# OErs_Drone.net
KiCad netlist of a schematic drawn in Altium Designer
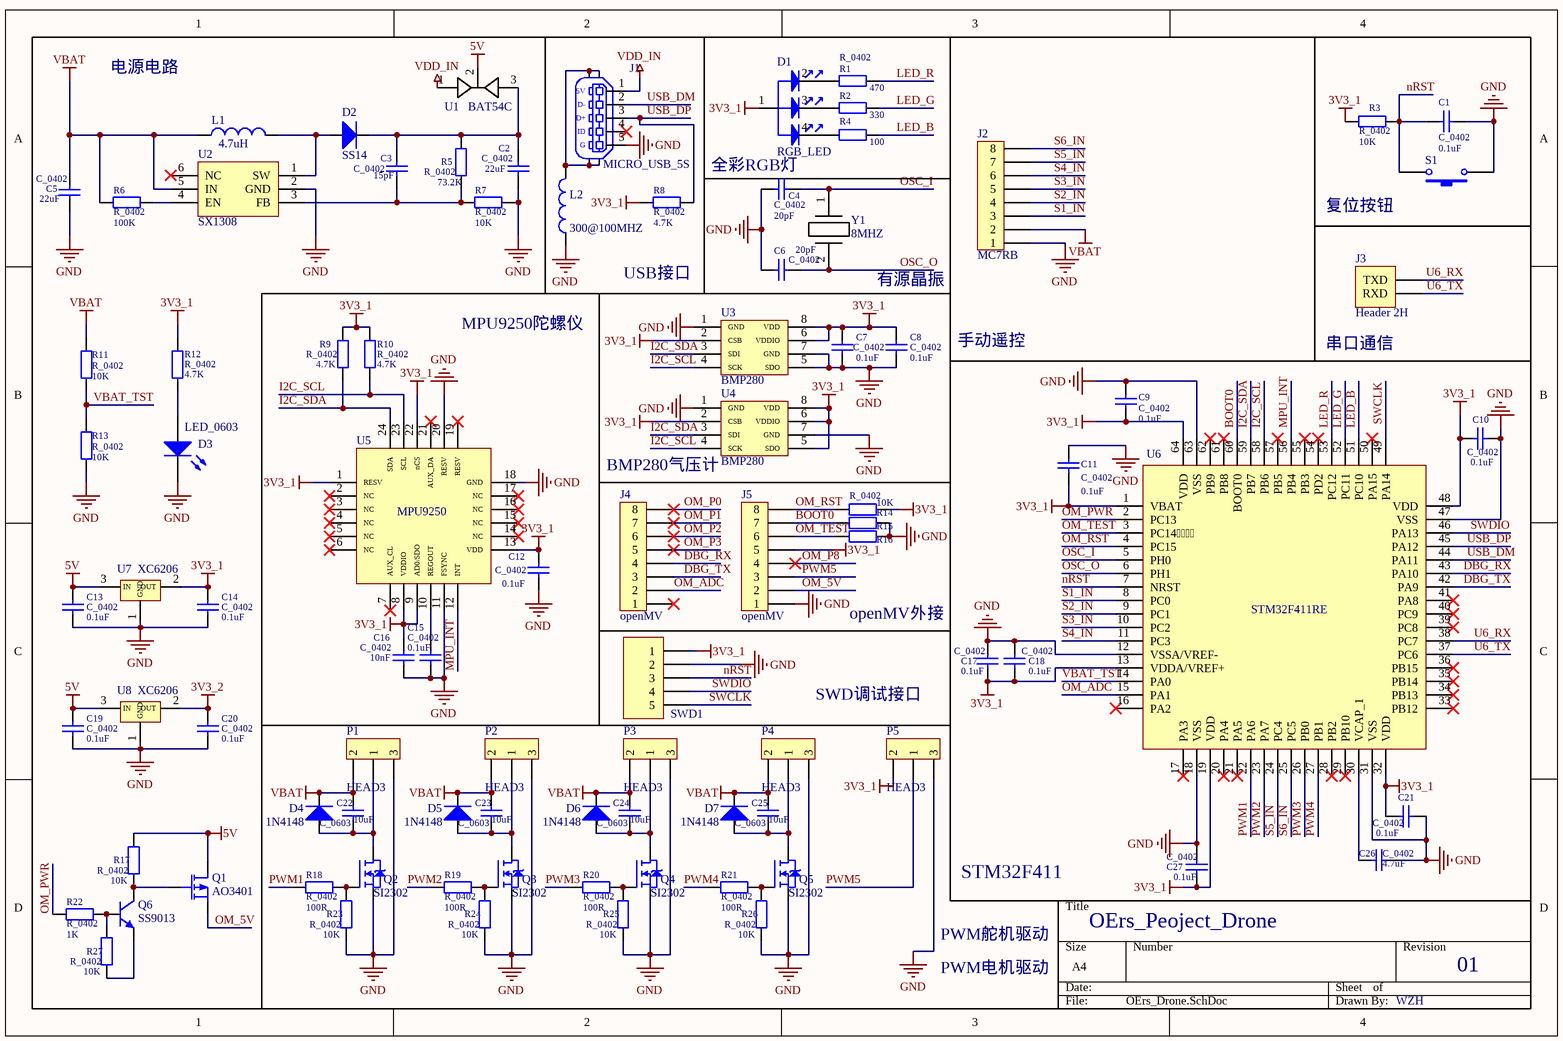
[diagram p0: OErs_Drone.SchDoc]

(export (version "E")
  (design (tool "Eeschema 10.0.6"))
  (components
    (comp (ref "C1")
      (value "C_0402")
      (footprint "C0402")
      (description "Capacitor")
      (fields (field (name "ALTIUM_VALUE") "0.1uF") (field (name "PUBLISHER") "Altium Limited"))
      (libsource (lib "Miscellaneous Devices") (part "Cap"))
    )
    (comp (ref "C2")
      (value "C_0402")
      (footprint "C0402")
      (description "Capacitor")
      (fields (field (name "ALTIUM_VALUE") "22uF") (field (name "PUBLISHER") "Altium Limited"))
      (libsource (lib "Miscellaneous Devices") (part "Cap"))
    )
    (comp (ref "C3")
      (value "C_0402")
      (footprint "C0402")
      (description "Capacitor")
      (fields (field (name "ALTIUM_VALUE") "15pF") (field (name "PUBLISHER") "Altium Limited"))
      (libsource (lib "Miscellaneous Devices") (part "Cap"))
    )
    (comp (ref "C4")
      (value "C_0402")
      (footprint "C0402")
      (description "Capacitor")
      (fields (field (name "ALTIUM_VALUE") "20pF") (field (name "PUBLISHER") "Altium Limited"))
      (libsource (lib "Miscellaneous Devices") (part "Cap"))
    )
    (comp (ref "C5")
      (value "C_0402")
      (footprint "C0402")
      (description "Capacitor")
      (fields (field (name "ALTIUM_VALUE") "22uF") (field (name "PUBLISHER") "Altium Limited"))
      (libsource (lib "Miscellaneous Devices") (part "Cap"))
    )
    (comp (ref "C6")
      (value "C_0402")
      (footprint "C0402")
      (description "Capacitor")
      (fields (field (name "ALTIUM_VALUE") "20pF") (field (name "PUBLISHER") "Altium Limited"))
      (libsource (lib "Miscellaneous Devices") (part "Cap"))
    )
    (comp (ref "C7")
      (value "C_0402")
      (footprint "C0402")
      (description "Capacitor")
      (fields (field (name "ALTIUM_VALUE") "0.1uF") (field (name "PUBLISHER") "Altium Limited"))
      (libsource (lib "Miscellaneous Devices") (part "Cap"))
    )
    (comp (ref "C8")
      (value "C_0402")
      (footprint "C0402")
      (description "Capacitor")
      (fields (field (name "ALTIUM_VALUE") "0.1uF") (field (name "PUBLISHER") "Altium Limited"))
      (libsource (lib "Miscellaneous Devices") (part "Cap"))
    )
    (comp (ref "C9")
      (value "C_0402")
      (footprint "C0402")
      (description "Capacitor")
      (fields (field (name "ALTIUM_VALUE") "0.1uF") (field (name "PUBLISHER") "Altium Limited"))
      (libsource (lib "Miscellaneous Devices") (part "Cap"))
    )
    (comp (ref "C10")
      (value "C_0402")
      (footprint "C0402")
      (description "Capacitor")
      (fields (field (name "ALTIUM_VALUE") "0.1uF") (field (name "PUBLISHER") "Altium Limited"))
      (libsource (lib "Miscellaneous Devices") (part "Cap"))
    )
    (comp (ref "C11")
      (value "C_0402")
      (footprint "C0402")
      (description "Capacitor")
      (fields (field (name "ALTIUM_VALUE") "0.1uF") (field (name "PUBLISHER") "Altium Limited"))
      (libsource (lib "Miscellaneous Devices") (part "Cap"))
    )
    (comp (ref "C12")
      (value "C_0402")
      (footprint "C0402")
      (description "Capacitor")
      (fields (field (name "ALTIUM_VALUE") "0.1uF") (field (name "PUBLISHER") "Altium Limited"))
      (libsource (lib "Miscellaneous Devices") (part "Cap"))
    )
    (comp (ref "C13")
      (value "C_0402")
      (footprint "C0402")
      (description "Capacitor")
      (fields (field (name "ALTIUM_VALUE") "0.1uF") (field (name "PUBLISHER") "Altium Limited"))
      (libsource (lib "Miscellaneous Devices") (part "Cap"))
    )
    (comp (ref "C14")
      (value "C_0402")
      (footprint "C0402")
      (description "Capacitor")
      (fields (field (name "ALTIUM_VALUE") "0.1uF") (field (name "PUBLISHER") "Altium Limited"))
      (libsource (lib "Miscellaneous Devices") (part "Cap"))
    )
    (comp (ref "C15")
      (value "C_0402")
      (footprint "C0402")
      (description "Capacitor")
      (fields (field (name "ALTIUM_VALUE") "0.1uF") (field (name "PUBLISHER") "Altium Limited"))
      (libsource (lib "Miscellaneous Devices") (part "Cap"))
    )
    (comp (ref "C16")
      (value "C_0402")
      (footprint "C0402")
      (description "Capacitor")
      (fields (field (name "ALTIUM_VALUE") "10nF") (field (name "PUBLISHER") "Altium Limited"))
      (libsource (lib "Miscellaneous Devices") (part "Cap"))
    )
    (comp (ref "C17")
      (value "C_0402")
      (footprint "C0402")
      (description "Capacitor")
      (fields (field (name "ALTIUM_VALUE") "0.1uF") (field (name "PUBLISHER") "Altium Limited"))
      (libsource (lib "Miscellaneous Devices") (part "Cap"))
    )
    (comp (ref "C18")
      (value "C_0402")
      (footprint "C0402")
      (description "Capacitor")
      (fields (field (name "ALTIUM_VALUE") "0.1uF") (field (name "PUBLISHER") "Altium Limited"))
      (libsource (lib "Miscellaneous Devices") (part "Cap"))
    )
    (comp (ref "C19")
      (value "C_0402")
      (footprint "C0402")
      (description "Capacitor")
      (fields (field (name "ALTIUM_VALUE") "0.1uF") (field (name "PUBLISHER") "Altium Limited"))
      (libsource (lib "Miscellaneous Devices") (part "Cap"))
    )
    (comp (ref "C20")
      (value "C_0402")
      (footprint "C0402")
      (description "Capacitor")
      (fields (field (name "ALTIUM_VALUE") "0.1uF") (field (name "PUBLISHER") "Altium Limited"))
      (libsource (lib "Miscellaneous Devices") (part "Cap"))
    )
    (comp (ref "C21")
      (value "C_0402")
      (footprint "C0402")
      (description "Capacitor")
      (fields (field (name "ALTIUM_VALUE") "0.1uF") (field (name "PUBLISHER") "Altium Limited"))
      (libsource (lib "Miscellaneous Devices") (part "Cap"))
    )
    (comp (ref "C22")
      (value "C_0603")
      (footprint "C0603")
      (description "Capacitor")
      (fields (field (name "ALTIUM_VALUE") "10uF") (field (name "PUBLISHER") "Altium Limited"))
      (libsource (lib "Miscellaneous Devices") (part "Cap"))
    )
    (comp (ref "C23")
      (value "C_0603")
      (footprint "C0603")
      (description "Capacitor")
      (fields (field (name "ALTIUM_VALUE") "10uF") (field (name "PUBLISHER") "Altium Limited"))
      (libsource (lib "Miscellaneous Devices") (part "Cap"))
    )
    (comp (ref "C24")
      (value "C_0603")
      (footprint "C0603")
      (description "Capacitor")
      (fields (field (name "ALTIUM_VALUE") "10uF") (field (name "PUBLISHER") "Altium Limited"))
      (libsource (lib "Miscellaneous Devices") (part "Cap"))
    )
    (comp (ref "C25")
      (value "C_0603")
      (footprint "C0603")
      (description "Capacitor")
      (fields (field (name "ALTIUM_VALUE") "10uF") (field (name "PUBLISHER") "Altium Limited"))
      (libsource (lib "Miscellaneous Devices") (part "Cap"))
    )
    (comp (ref "C26")
      (value "C_0402")
      (footprint "C0402")
      (description "Capacitor")
      (fields (field (name "ALTIUM_VALUE") "4.7uF") (field (name "PUBLISHER") "Altium Limited"))
      (libsource (lib "Miscellaneous Devices") (part "Cap"))
    )
    (comp (ref "C27")
      (value "C_0402")
      (footprint "C0402")
      (description "Capacitor")
      (fields (field (name "ALTIUM_VALUE") "0.1uF") (field (name "PUBLISHER") "Altium Limited"))
      (libsource (lib "Miscellaneous Devices") (part "Cap"))
    )
    (comp (ref "D1")
      (value "RGB_LED")
      (footprint "LED-RGB")
      (description "全彩RGB")
      (libsource (lib "OErs_Drone") (part "RGB_LED"))
    )
    (comp (ref "D2")
      (value "SS14")
      (footprint "SMA_L4.4-W2.8-LS5.4-RD")
      (description "Default Diode")
      (fields (field (name "PUBLISHER") "Altium Limited"))
      (libsource (lib "Miscellaneous Devices") (part "Diode"))
    )
    (comp (ref "D3")
      (value "LED_0603")
      (footprint "LED0603-FD")
      (description "Typical RED, GREEN, YELLOW, AMBER GaAs LED")
      (fields (field (name "PUBLISHER") "Altium Limited"))
      (libsource (lib "Miscellaneous Devices") (part "LED2"))
    )
    (comp (ref "D4")
      (value "1N4148")
      (footprint "SOD-123_L2.8-W1.8-LS3.7-RD")
      (description "Default Diode")
      (fields (field (name "PUBLISHER") "Altium Limited"))
      (libsource (lib "Miscellaneous Devices") (part "Diode"))
    )
    (comp (ref "D5")
      (value "1N4148")
      (footprint "SOD-123_L2.8-W1.8-LS3.7-RD")
      (description "Default Diode")
      (fields (field (name "PUBLISHER") "Altium Limited"))
      (libsource (lib "Miscellaneous Devices") (part "Diode"))
    )
    (comp (ref "D6")
      (value "1N4148")
      (footprint "SOD-123_L2.8-W1.8-LS3.7-RD")
      (description "Default Diode")
      (fields (field (name "PUBLISHER") "Altium Limited"))
      (libsource (lib "Miscellaneous Devices") (part "Diode"))
    )
    (comp (ref "D7")
      (value "1N4148")
      (footprint "SOD-123_L2.8-W1.8-LS3.7-RD")
      (description "Default Diode")
      (fields (field (name "PUBLISHER") "Altium Limited"))
      (libsource (lib "Miscellaneous Devices") (part "Diode"))
    )
    (comp (ref "J1")
      (value "MICRO_USB_5S")
      (footprint "MICRO-USB-SMD_U254-051T-4BH83-F1S")
      (description "USB接口")
      (libsource (lib "OErs_Drone") (part "MICRO_USB_5S"))
    )
    (comp (ref "J2")
      (value "MC7RB")
      (footprint "HDR1X8")
      (description "外接")
      (libsource (lib "OErs_Drone") (part "openMV"))
    )
    (comp (ref "J3")
      (value "Header 2H")
      (footprint "HDR1X2")
      (description "Header, 2-Pin, Right Angle")
      (fields (field (name "PUBLISHER") "Altium Limited"))
      (libsource (lib "Miscellaneous Connectors") (part "Header 2H"))
    )
    (comp (ref "J4")
      (value "openMV")
      (footprint "HDR1X8")
      (description "外接openmv模组")
      (libsource (lib "OErs_Drone") (part "openMV"))
    )
    (comp (ref "J5")
      (value "openMV")
      (footprint "HDR1X8")
      (description "外接openmv模组")
      (libsource (lib "OErs_Drone") (part "openMV"))
    )
    (comp (ref "L1")
      (value "4.7uH")
      (footprint "0603")
      (description "Inductor")
      (fields (field (name "PUBLISHER") "Altium Limited"))
      (libsource (lib "Miscellaneous Devices") (part "Inductor"))
    )
    (comp (ref "L2")
      (value "300@100MHZ")
      (footprint "0603")
      (description "Inductor")
      (fields (field (name "PUBLISHER") "Altium Limited"))
      (libsource (lib "Miscellaneous Devices") (part "Inductor"))
    )
    (comp (ref "P1")
      (value "HEAD3")
      (footprint "HDR1X3")
      (description "3脚插口")
      (libsource (lib "OErs_Drone") (part "HEAD3"))
    )
    (comp (ref "P2")
      (value "HEAD3")
      (footprint "HDR1X3")
      (description "3脚插口")
      (libsource (lib "OErs_Drone") (part "HEAD3"))
    )
    (comp (ref "P3")
      (value "HEAD3")
      (footprint "HDR1X3")
      (description "3脚插口")
      (libsource (lib "OErs_Drone") (part "HEAD3"))
    )
    (comp (ref "P4")
      (value "HEAD3")
      (footprint "HDR1X3")
      (description "3脚插口")
      (libsource (lib "OErs_Drone") (part "HEAD3"))
    )
    (comp (ref "P5")
      (value "HEAD3")
      (footprint "HDR1X3")
      (description "3脚插口")
      (libsource (lib "OErs_Drone") (part "HEAD3"))
    )
    (comp (ref "Q1")
      (value "AO3401")
      (footprint "SOT-23-3_L2.9-W1.3-P1.90-LS2.4-BR")
      (description "P-Channel MOSFET")
      (fields (field (name "PUBLISHER") "Altium Limited"))
      (libsource (lib "Miscellaneous Devices") (part "MOSFET-P"))
    )
    (comp (ref "Q2")
      (value "SI2302")
      (footprint "SOT-23-3_L2.9-W1.3-P1.90-LS2.4-BR")
      (description "N-Channel MOSFET")
      (libsource (lib "General") (part "FDB52N20"))
    )
    (comp (ref "Q3")
      (value "SI2302")
      (footprint "SOT-23-3_L2.9-W1.3-P1.90-LS2.4-BR")
      (description "N-Channel MOSFET")
      (libsource (lib "General") (part "FDB52N20"))
    )
    (comp (ref "Q4")
      (value "SI2302")
      (footprint "SOT-23-3_L2.9-W1.3-P1.90-LS2.4-BR")
      (description "N-Channel MOSFET")
      (libsource (lib "General") (part "FDB52N20"))
    )
    (comp (ref "Q5")
      (value "SI2302")
      (footprint "SOT-23-3_L2.9-W1.3-P1.90-LS2.4-BR")
      (description "N-Channel MOSFET")
      (libsource (lib "General") (part "FDB52N20"))
    )
    (comp (ref "Q6")
      (value "SS9013")
      (footprint "TO-92A")
      (description "NPN General Purpose Amplifier")
      (fields (field (name "PUBLISHER") "Altium Limited"))
      (libsource (lib "Miscellaneous Devices") (part "2N3904"))
    )
    (comp (ref "R1")
      (value "R_0402")
      (footprint "R0402")
      (description "Resistor")
      (fields (field (name "ALTIUM_VALUE") "470") (field (name "PUBLISHER") "Altium Limited"))
      (libsource (lib "Miscellaneous Devices") (part "Res2"))
    )
    (comp (ref "R2")
      (value "330")
      (footprint "R0402")
      (description "Resistor")
      (fields (field (name "Comment") "R_0402") (field (name "PUBLISHER") "Altium Limited"))
      (libsource (lib "Miscellaneous Devices") (part "Res2"))
    )
    (comp (ref "R3")
      (value "R_0402")
      (footprint "R0402")
      (description "Resistor")
      (fields (field (name "ALTIUM_VALUE") "10K") (field (name "PUBLISHER") "Altium Limited"))
      (libsource (lib "Miscellaneous Devices") (part "Res2"))
    )
    (comp (ref "R4")
      (value "100")
      (footprint "R0402")
      (description "Resistor")
      (fields (field (name "Comment") "R_0402") (field (name "PUBLISHER") "Altium Limited"))
      (libsource (lib "Miscellaneous Devices") (part "Res2"))
    )
    (comp (ref "R5")
      (value "R_0402")
      (footprint "R0402")
      (description "Resistor")
      (fields (field (name "ALTIUM_VALUE") "73.2K") (field (name "PUBLISHER") "Altium Limited"))
      (libsource (lib "") (part "Res2_1"))
    )
    (comp (ref "R6")
      (value "R_0402")
      (footprint "R0402")
      (description "Resistor")
      (fields (field (name "ALTIUM_VALUE") "100K") (field (name "PUBLISHER") "Altium Limited"))
      (libsource (lib "Miscellaneous Devices") (part "Res2"))
    )
    (comp (ref "R7")
      (value "R_0402")
      (footprint "R0402")
      (description "Resistor")
      (fields (field (name "ALTIUM_VALUE") "10K") (field (name "PUBLISHER") "Altium Limited"))
      (libsource (lib "Miscellaneous Devices") (part "Res2"))
    )
    (comp (ref "R8")
      (value "R_0402")
      (footprint "R0402")
      (description "Resistor")
      (fields (field (name "ALTIUM_VALUE") "4.7K") (field (name "PUBLISHER") "Altium Limited"))
      (libsource (lib "Miscellaneous Devices") (part "Res2"))
    )
    (comp (ref "R9")
      (value "R_0402")
      (footprint "R0402")
      (description "Resistor")
      (fields (field (name "ALTIUM_VALUE") "4.7K") (field (name "PUBLISHER") "Altium Limited"))
      (libsource (lib "") (part "Res2_1"))
    )
    (comp (ref "R10")
      (value "R_0402")
      (footprint "R0402")
      (description "Resistor")
      (fields (field (name "ALTIUM_VALUE") "4.7K") (field (name "PUBLISHER") "Altium Limited"))
      (libsource (lib "") (part "Res2_1"))
    )
    (comp (ref "R11")
      (value "R_0402")
      (footprint "R0402")
      (description "Resistor")
      (fields (field (name "ALTIUM_VALUE") "10K") (field (name "PUBLISHER") "Altium Limited"))
      (libsource (lib "") (part "Res2_2"))
    )
    (comp (ref "R12")
      (value "R_0402")
      (footprint "R0402")
      (description "Resistor")
      (fields (field (name "ALTIUM_VALUE") "4.7K") (field (name "PUBLISHER") "Altium Limited"))
      (libsource (lib "") (part "Res2_1"))
    )
    (comp (ref "R13")
      (value "R_0402")
      (footprint "R0402")
      (description "Resistor")
      (fields (field (name "ALTIUM_VALUE") "10K") (field (name "PUBLISHER") "Altium Limited"))
      (libsource (lib "") (part "Res2_2"))
    )
    (comp (ref "R14")
      (value "R_0402")
      (footprint "R0402")
      (description "Resistor")
      (fields (field (name "ALTIUM_VALUE") "10K") (field (name "PUBLISHER") "Altium Limited"))
      (libsource (lib "Miscellaneous Devices") (part "Res2"))
    )
    (comp (ref "R15")
      (value "R_0402")
      (footprint "R0402")
      (description "Resistor")
      (fields (field (name "PUBLISHER") "Altium Limited"))
      (libsource (lib "Miscellaneous Devices") (part "Res2"))
    )
    (comp (ref "R16")
      (value "R_0402")
      (footprint "R0402")
      (description "Resistor")
      (fields (field (name "PUBLISHER") "Altium Limited"))
      (libsource (lib "Miscellaneous Devices") (part "Res2"))
    )
    (comp (ref "R17")
      (value "R_0402")
      (footprint "R0402")
      (description "Resistor")
      (fields (field (name "ALTIUM_VALUE") "10K") (field (name "PUBLISHER") "Altium Limited"))
      (libsource (lib "") (part "Res2_1"))
    )
    (comp (ref "R18")
      (value "R_0402")
      (footprint "R0402")
      (description "Resistor")
      (fields (field (name "ALTIUM_VALUE") "100R") (field (name "PUBLISHER") "Altium Limited"))
      (libsource (lib "Miscellaneous Devices") (part "Res2"))
    )
    (comp (ref "R19")
      (value "R_0402")
      (footprint "R0402")
      (description "Resistor")
      (fields (field (name "ALTIUM_VALUE") "100R") (field (name "PUBLISHER") "Altium Limited"))
      (libsource (lib "Miscellaneous Devices") (part "Res2"))
    )
    (comp (ref "R20")
      (value "R_0402")
      (footprint "R0402")
      (description "Resistor")
      (fields (field (name "ALTIUM_VALUE") "100R") (field (name "PUBLISHER") "Altium Limited"))
      (libsource (lib "Miscellaneous Devices") (part "Res2"))
    )
    (comp (ref "R21")
      (value "R_0402")
      (footprint "R0402")
      (description "Resistor")
      (fields (field (name "ALTIUM_VALUE") "100R") (field (name "PUBLISHER") "Altium Limited"))
      (libsource (lib "Miscellaneous Devices") (part "Res2"))
    )
    (comp (ref "R22")
      (value "R_0402")
      (footprint "R0402")
      (description "Resistor")
      (fields (field (name "ALTIUM_VALUE") "1K") (field (name "PUBLISHER") "Altium Limited"))
      (libsource (lib "Miscellaneous Devices") (part "Res2"))
    )
    (comp (ref "R23")
      (value "R_0402")
      (footprint "R0402")
      (description "Resistor")
      (fields (field (name "ALTIUM_VALUE") "10K") (field (name "PUBLISHER") "Altium Limited"))
      (libsource (lib "") (part "Res2_1"))
    )
    (comp (ref "R24")
      (value "R_0402")
      (footprint "R0402")
      (description "Resistor")
      (fields (field (name "ALTIUM_VALUE") "10K") (field (name "PUBLISHER") "Altium Limited"))
      (libsource (lib "") (part "Res2_1"))
    )
    (comp (ref "R25")
      (value "R_0402")
      (footprint "R0402")
      (description "Resistor")
      (fields (field (name "ALTIUM_VALUE") "10K") (field (name "PUBLISHER") "Altium Limited"))
      (libsource (lib "") (part "Res2_1"))
    )
    (comp (ref "R26")
      (value "R_0402")
      (footprint "R0402")
      (description "Resistor")
      (fields (field (name "ALTIUM_VALUE") "10K") (field (name "PUBLISHER") "Altium Limited"))
      (libsource (lib "") (part "Res2_1"))
    )
    (comp (ref "R27")
      (value "R_0402")
      (footprint "R0402")
      (description "Resistor")
      (fields (field (name "ALTIUM_VALUE") "10K") (field (name "PUBLISHER") "Altium Limited"))
      (libsource (lib "") (part "Res2_1"))
    )
    (comp (ref "S1")
      (value "667")
      (footprint "KEY-TH_4P-L6.0-W6.0-P4.50-LS6.5")
      (description "Switch")
      (fields (field (name "PUBLISHER") "Altium Limited"))
      (libsource (lib "Miscellaneous Devices") (part "SW-PB"))
    )
    (comp (ref "SWD1")
      (value "SWD")
      (footprint "HDR1X5")
      (description "Header, 5-Pin")
      (fields (field (name "PUBLISHER") "Altium Limited"))
      (libsource (lib "OErs_Drone") (part "SWD"))
    )
    (comp (ref "U1")
      (value "BAT54C")
      (footprint "SOT-23-3_L2.9-W1.6-P1.90-LS2.8-BR")
      (description "二通一限流")
      (libsource (lib "OErs_Drone") (part "BAT54C"))
    )
    (comp (ref "U2")
      (value "SX1308")
      (footprint "SOT-23-6_L2.9-W1.6-P0.95-LS2.8-BR")
      (description "电源控制")
      (libsource (lib "OErs_Drone") (part "SX1308"))
    )
    (comp (ref "U3")
      (value "BMP280")
      (footprint "SENSOR-TH_BMP280-BL")
      (description "气压计")
      (libsource (lib "OErs_Drone") (part "BMP280"))
    )
    (comp (ref "U4")
      (value "BMP280")
      (footprint "SENSOR-TH_BMP280-BL")
      (description "气压计")
      (libsource (lib "OErs_Drone") (part "BMP280"))
    )
    (comp (ref "U5")
      (value "MPU9250")
      (footprint "MPU9250")
      (description "9轴陀螺仪传感器")
      (libsource (lib "OErs_Drone") (part "MPU9250"))
    )
    (comp (ref "U6")
      (value "STM32F411RE")
      (footprint "LQFP-64_L10.0-W10.0-P0.50-LS12.0-BL")
      (description "单片机")
      (libsource (lib "OErs_Drone") (part "STM32F411RE"))
    )
    (comp (ref "U7")
      (value "XC6206")
      (footprint "SOT-23-3_L3.0-W1.7-P0.95-LS2.9-BR")
      (description "5to3.3")
      (libsource (lib "OErs_Drone") (part "XC6206"))
    )
    (comp (ref "U8")
      (value "XC6206")
      (footprint "SOT-23-3_L3.0-W1.7-P0.95-LS2.9-BR")
      (description "5to3.3")
      (libsource (lib "OErs_Drone") (part "XC6206"))
    )
    (comp (ref "Y1")
      (value "8MHZ")
      (footprint "OSC-SMD_L5.0-W3.2")
      (description "晶振")
      (libsource (lib "OErs_Drone") (part "SMD5032"))
    )
  )
  (nets
    (net (code "1") (name "/BOOT0") (class "Default")
      (node (ref "J5") (pin "7") (pinfunction "7_7") (pintype "passive"))
      (node (ref "R15") (pin "2") (pinfunction "2_2") (pintype "passive"))
      (node (ref "U6") (pin "60") (pinfunction "BOOT0_60") (pintype "passive"))
    )
    (net (code "2") (name "/DBG_RX") (class "Default")
      (node (ref "J4") (pin "4") (pinfunction "4_4") (pintype "passive"))
      (node (ref "U6") (pin "43") (pinfunction "PA10_43") (pintype "passive"))
    )
    (net (code "3") (name "/DBG_TX") (class "Default")
      (node (ref "J4") (pin "3") (pinfunction "3_3") (pintype "passive"))
      (node (ref "U6") (pin "42") (pinfunction "PA9_42") (pintype "passive"))
    )
    (net (code "4") (name "/I2C_SCL") (class "Default")
      (node (ref "R10") (pin "1") (pinfunction "1_1") (pintype "passive"))
      (node (ref "U3") (pin "4") (pinfunction "SCK_4") (pintype "passive"))
      (node (ref "U4") (pin "4") (pinfunction "SCK_4") (pintype "passive"))
      (node (ref "U5") (pin "23") (pinfunction "SCL_23") (pintype "passive"))
      (node (ref "U6") (pin "58") (pinfunction "PB6_58") (pintype "passive"))
    )
    (net (code "5") (name "/I2C_SDA") (class "Default")
      (node (ref "R9") (pin "1") (pinfunction "1_1") (pintype "passive"))
      (node (ref "U3") (pin "3") (pinfunction "SDI_3") (pintype "passive"))
      (node (ref "U4") (pin "3") (pinfunction "SDI_3") (pintype "passive"))
      (node (ref "U5") (pin "24") (pinfunction "SDA_24") (pintype "passive"))
      (node (ref "U6") (pin "59") (pinfunction "PB7_59") (pintype "passive"))
    )
    (net (code "6") (name "/LED_B") (class "Default")
      (node (ref "R4") (pin "1") (pinfunction "1_1") (pintype "passive"))
      (node (ref "U6") (pin "51") (pinfunction "PC10_51") (pintype "passive"))
    )
    (net (code "7") (name "/LED_G") (class "Default")
      (node (ref "R2") (pin "1") (pinfunction "1_1") (pintype "passive"))
      (node (ref "U6") (pin "52") (pinfunction "PC11_52") (pintype "passive"))
    )
    (net (code "8") (name "/LED_R") (class "Default")
      (node (ref "R1") (pin "1") (pinfunction "1_1") (pintype "passive"))
      (node (ref "U6") (pin "53") (pinfunction "PC12_53") (pintype "passive"))
    )
    (net (code "9") (name "/MPU_INT") (class "Default")
      (node (ref "U5") (pin "12") (pinfunction "INT_12") (pintype "passive"))
      (node (ref "U6") (pin "56") (pinfunction "PB4_56") (pintype "passive"))
    )
    (net (code "10") (name "/OM_5V") (class "Default")
      (node (ref "J5") (pin "2") (pinfunction "2_2") (pintype "passive"))
      (node (ref "Q1") (pin "2") (pinfunction "S_2") (pintype "passive"))
    )
    (net (code "11") (name "/OM_ADC") (class "Default")
      (node (ref "J4") (pin "2") (pinfunction "2_2") (pintype "passive"))
      (node (ref "U6") (pin "15") (pinfunction "PA1_15") (pintype "passive"))
    )
    (net (code "12") (name "/OM_P0") (class "Default")
      (node (ref "J4") (pin "8") (pinfunction "8_8") (pintype "passive+no_connect"))
    )
    (net (code "13") (name "/OM_P1") (class "Default")
      (node (ref "J4") (pin "7") (pinfunction "7_7") (pintype "passive+no_connect"))
    )
    (net (code "14") (name "/OM_P2") (class "Default")
      (node (ref "J4") (pin "6") (pinfunction "6_6") (pintype "passive+no_connect"))
    )
    (net (code "15") (name "/OM_P3") (class "Default")
      (node (ref "J4") (pin "5") (pinfunction "5_5") (pintype "passive+no_connect"))
    )
    (net (code "16") (name "/OM_P8") (class "Default")
      (node (ref "J5") (pin "4") (pinfunction "4_4") (pintype "passive+no_connect"))
    )
    (net (code "17") (name "/OM_PWR") (class "Default")
      (node (ref "R22") (pin "2") (pinfunction "2_2") (pintype "passive"))
      (node (ref "U6") (pin "2") (pinfunction "PC13_2") (pintype "passive"))
    )
    (net (code "18") (name "/OM_RST") (class "Default")
      (node (ref "J5") (pin "8") (pinfunction "8_8") (pintype "passive"))
      (node (ref "R14") (pin "2") (pinfunction "2_2") (pintype "passive"))
      (node (ref "U6") (pin "4") (pinfunction "PC15_4") (pintype "passive"))
    )
    (net (code "19") (name "/OM_TEST") (class "Default")
      (node (ref "J5") (pin "6") (pinfunction "6_6") (pintype "passive"))
      (node (ref "R16") (pin "2") (pinfunction "2_2") (pintype "passive"))
      (node (ref "U6") (pin "3") (pinfunction "PC14_3") (pintype "passive"))
    )
    (net (code "20") (name "/OSC_I") (class "Default")
      (node (ref "C4") (pin "1") (pinfunction "1_1") (pintype "passive"))
      (node (ref "U6") (pin "5") (pinfunction "PH0_5") (pintype "passive"))
      (node (ref "Y1") (pin "1") (pinfunction "1_1") (pintype "passive"))
    )
    (net (code "21") (name "/OSC_O") (class "Default")
      (node (ref "C6") (pin "1") (pinfunction "1_1") (pintype "passive"))
      (node (ref "U6") (pin "6") (pinfunction "PH1_6") (pintype "passive"))
      (node (ref "Y1") (pin "2") (pinfunction "2_2") (pintype "passive"))
    )
    (net (code "22") (name "/PWM1") (class "Default")
      (node (ref "R18") (pin "2") (pinfunction "2_2") (pintype "passive"))
      (node (ref "U6") (pin "22") (pinfunction "PA6_22") (pintype "passive"))
    )
    (net (code "23") (name "/PWM2") (class "Default")
      (node (ref "R19") (pin "2") (pinfunction "2_2") (pintype "passive"))
      (node (ref "U6") (pin "23") (pinfunction "PA7_23") (pintype "passive"))
    )
    (net (code "24") (name "/PWM3") (class "Default")
      (node (ref "R20") (pin "2") (pinfunction "2_2") (pintype "passive"))
      (node (ref "U6") (pin "26") (pinfunction "PB0_26") (pintype "passive"))
    )
    (net (code "25") (name "/PWM4") (class "Default")
      (node (ref "R21") (pin "2") (pinfunction "2_2") (pintype "passive"))
      (node (ref "U6") (pin "27") (pinfunction "PB1_27") (pintype "passive"))
    )
    (net (code "26") (name "/PWM5") (class "Default")
      (node (ref "J5") (pin "3") (pinfunction "3_3") (pintype "passive"))
      (node (ref "P5") (pin "1") (pinfunction "1_1") (pintype "passive"))
    )
    (net (code "27") (name "/S1_IN") (class "Default")
      (node (ref "J2") (pin "3") (pinfunction "3_3") (pintype "passive"))
      (node (ref "U6") (pin "8") (pinfunction "PC0_8") (pintype "passive"))
    )
    (net (code "28") (name "/S2_IN") (class "Default")
      (node (ref "J2") (pin "4") (pinfunction "4_4") (pintype "passive"))
      (node (ref "U6") (pin "9") (pinfunction "PC1_9") (pintype "passive"))
    )
    (net (code "29") (name "/S3_IN") (class "Default")
      (node (ref "J2") (pin "5") (pinfunction "5_5") (pintype "passive"))
      (node (ref "U6") (pin "10") (pinfunction "PC2_10") (pintype "passive"))
    )
    (net (code "30") (name "/S4_IN") (class "Default")
      (node (ref "J2") (pin "6") (pinfunction "6_6") (pintype "passive"))
      (node (ref "U6") (pin "11") (pinfunction "PC3_11") (pintype "passive"))
    )
    (net (code "31") (name "/S5_IN") (class "Default")
      (node (ref "J2") (pin "7") (pinfunction "7_7") (pintype "passive"))
      (node (ref "U6") (pin "24") (pinfunction "PC4_24") (pintype "passive"))
    )
    (net (code "32") (name "/S6_IN") (class "Default")
      (node (ref "J2") (pin "8") (pinfunction "8_8") (pintype "passive"))
      (node (ref "U6") (pin "25") (pinfunction "PC5_25") (pintype "passive"))
    )
    (net (code "33") (name "/SWCLK") (class "Default")
      (node (ref "SWD1") (pin "5") (pinfunction "5_5") (pintype "passive"))
      (node (ref "U6") (pin "49") (pinfunction "PA14_49") (pintype "passive"))
    )
    (net (code "34") (name "/SWDIO") (class "Default")
      (node (ref "SWD1") (pin "4") (pinfunction "4_4") (pintype "passive"))
      (node (ref "U6") (pin "46") (pinfunction "PA13_46") (pintype "passive"))
    )
    (net (code "35") (name "/U6_RX") (class "Default")
      (node (ref "J3") (pin "2") (pinfunction "TXD_2") (pintype "passive"))
      (node (ref "U6") (pin "38") (pinfunction "PC7_38") (pintype "passive"))
    )
    (net (code "36") (name "/U6_TX") (class "Default")
      (node (ref "J3") (pin "1") (pinfunction "RXD_1") (pintype "passive"))
      (node (ref "U6") (pin "37") (pinfunction "PC6_37") (pintype "passive"))
    )
    (net (code "37") (name "/USB_DM") (class "Default")
      (node (ref "J1") (pin "2") (pinfunction "D-_2") (pintype "passive"))
      (node (ref "U6") (pin "44") (pinfunction "PA11_44") (pintype "passive"))
    )
    (net (code "38") (name "/USB_DP") (class "Default")
      (node (ref "J1") (pin "3") (pinfunction "D+_3") (pintype "passive"))
      (node (ref "R8") (pin "1") (pinfunction "1_1") (pintype "passive"))
      (node (ref "U6") (pin "45") (pinfunction "PA12_45") (pintype "passive"))
    )
    (net (code "39") (name "/VBAT_TST") (class "Default")
      (node (ref "R11") (pin "2") (pinfunction "2_2") (pintype "passive"))
      (node (ref "R13") (pin "1") (pinfunction "1_1") (pintype "passive"))
      (node (ref "U6") (pin "14") (pinfunction "PA0_14") (pintype "passive"))
    )
    (net (code "40") (name "/nRST") (class "Default")
      (node (ref "C1") (pin "2") (pinfunction "2_2") (pintype "passive"))
      (node (ref "R3") (pin "1") (pinfunction "1_1") (pintype "passive"))
      (node (ref "S1") (pin "3") (pinfunction "3_3") (pintype "passive"))
      (node (ref "SWD1") (pin "3") (pinfunction "3_3") (pintype "passive"))
      (node (ref "U6") (pin "7") (pinfunction "NRST_7") (pintype "passive"))
    )
    (net (code "41") (name "3V3_1") (class "Default")
      (node (ref "C10") (pin "1") (pinfunction "1_1") (pintype "passive"))
      (node (ref "C11") (pin "1") (pinfunction "1_1") (pintype "passive"))
      (node (ref "C12") (pin "2") (pinfunction "2_2") (pintype "passive"))
      (node (ref "C14") (pin "2") (pinfunction "2_2") (pintype "passive"))
      (node (ref "C16") (pin "2") (pinfunction "2_2") (pintype "passive"))
      (node (ref "C17") (pin "1") (pinfunction "1_1") (pintype "passive"))
      (node (ref "C18") (pin "1") (pinfunction "1_1") (pintype "passive"))
      (node (ref "C21") (pin "2") (pinfunction "2_2") (pintype "passive"))
      (node (ref "C27") (pin "2") (pinfunction "2_2") (pintype "passive"))
      (node (ref "C7") (pin "2") (pinfunction "2_2") (pintype "passive"))
      (node (ref "C8") (pin "2") (pinfunction "2_2") (pintype "passive"))
      (node (ref "C9") (pin "1") (pinfunction "1_1") (pintype "passive"))
      (node (ref "D1") (pin "1") (pintype "passive"))
      (node (ref "J5") (pin "5") (pinfunction "5_5") (pintype "passive"))
      (node (ref "P5") (pin "2") (pinfunction "2_2") (pintype "passive"))
      (node (ref "R10") (pin "2") (pinfunction "2_2") (pintype "passive"))
      (node (ref "R12") (pin "2") (pinfunction "2_2") (pintype "passive"))
      (node (ref "R14") (pin "1") (pinfunction "1_1") (pintype "passive"))
      (node (ref "R3") (pin "2") (pinfunction "2_2") (pintype "passive"))
      (node (ref "R8") (pin "2") (pinfunction "2_2") (pintype "passive"))
      (node (ref "R9") (pin "2") (pinfunction "2_2") (pintype "passive"))
      (node (ref "SWD1") (pin "1") (pinfunction "1_1") (pintype "passive"))
      (node (ref "U3") (pin "2") (pinfunction "CSB_2") (pintype "passive"))
      (node (ref "U3") (pin "6") (pinfunction "VDDIO_6") (pintype "passive"))
      (node (ref "U3") (pin "8") (pinfunction "VDD_8") (pintype "passive"))
      (node (ref "U4") (pin "2") (pinfunction "CSB_2") (pintype "passive"))
      (node (ref "U4") (pin "5") (pinfunction "SDO_5") (pintype "passive"))
      (node (ref "U4") (pin "6") (pinfunction "VDDIO_6") (pintype "passive"))
      (node (ref "U4") (pin "8") (pinfunction "VDD_8") (pintype "passive"))
      (node (ref "U5") (pin "1") (pinfunction "RESV_1") (pintype "passive"))
      (node (ref "U5") (pin "13") (pinfunction "VDD_13") (pintype "passive"))
      (node (ref "U5") (pin "22") (pinfunction "nCS_22") (pintype "passive"))
      (node (ref "U5") (pin "8") (pinfunction "VDDIO_8") (pintype "passive"))
      (node (ref "U5") (pin "9") (pinfunction "AD0/SDO_9") (pintype "passive"))
      (node (ref "U6") (pin "1") (pinfunction "VBAT_1") (pintype "passive"))
      (node (ref "U6") (pin "13") (pinfunction "VDDA/VREF+_13") (pintype "passive"))
      (node (ref "U6") (pin "19") (pinfunction "VDD_19") (pintype "passive"))
      (node (ref "U6") (pin "32") (pinfunction "VDD_32") (pintype "passive"))
      (node (ref "U6") (pin "48") (pinfunction "VDD_48") (pintype "passive"))
      (node (ref "U6") (pin "64") (pinfunction "VDD_64") (pintype "passive"))
      (node (ref "U7") (pin "2") (pinfunction "OUT_2") (pintype "passive"))
    )
    (net (code "42") (name "3V3_2") (class "Default")
      (node (ref "C20") (pin "2") (pinfunction "2_2") (pintype "passive"))
      (node (ref "U8") (pin "2") (pinfunction "OUT_2") (pintype "passive"))
    )
    (net (code "43") (name "5V") (class "Default")
      (node (ref "C13") (pin "2") (pinfunction "2_2") (pintype "passive"))
      (node (ref "C19") (pin "2") (pinfunction "2_2") (pintype "passive"))
      (node (ref "Q1") (pin "3") (pinfunction "D_3") (pintype "passive"))
      (node (ref "R17") (pin "2") (pinfunction "2_2") (pintype "passive"))
      (node (ref "U1") (pin "2") (pinfunction "2_2") (pintype "passive"))
      (node (ref "U7") (pin "3") (pinfunction "IN_3") (pintype "passive"))
      (node (ref "U8") (pin "3") (pinfunction "IN_3") (pintype "passive"))
    )
    (net (code "44") (name "GND") (class "Default")
      (node (ref "C1") (pin "1") (pinfunction "1_1") (pintype "passive"))
      (node (ref "C10") (pin "2") (pinfunction "2_2") (pintype "passive"))
      (node (ref "C11") (pin "2") (pinfunction "2_2") (pintype "passive"))
      (node (ref "C12") (pin "1") (pinfunction "1_1") (pintype "passive"))
      (node (ref "C13") (pin "1") (pinfunction "1_1") (pintype "passive"))
      (node (ref "C14") (pin "1") (pinfunction "1_1") (pintype "passive"))
      (node (ref "C15") (pin "1") (pinfunction "1_1") (pintype "passive"))
      (node (ref "C16") (pin "1") (pinfunction "1_1") (pintype "passive"))
      (node (ref "C17") (pin "2") (pinfunction "2_2") (pintype "passive"))
      (node (ref "C18") (pin "2") (pinfunction "2_2") (pintype "passive"))
      (node (ref "C19") (pin "1") (pinfunction "1_1") (pintype "passive"))
      (node (ref "C2") (pin "1") (pinfunction "1_1") (pintype "passive"))
      (node (ref "C20") (pin "1") (pinfunction "1_1") (pintype "passive"))
      (node (ref "C21") (pin "1") (pinfunction "1_1") (pintype "passive"))
      (node (ref "C26") (pin "1") (pinfunction "1_1") (pintype "passive"))
      (node (ref "C27") (pin "1") (pinfunction "1_1") (pintype "passive"))
      (node (ref "C4") (pin "2") (pinfunction "2_2") (pintype "passive"))
      (node (ref "C5") (pin "1") (pinfunction "1_1") (pintype "passive"))
      (node (ref "C6") (pin "2") (pinfunction "2_2") (pintype "passive"))
      (node (ref "C7") (pin "1") (pinfunction "1_1") (pintype "passive"))
      (node (ref "C8") (pin "1") (pinfunction "1_1") (pintype "passive"))
      (node (ref "C9") (pin "2") (pinfunction "2_2") (pintype "passive"))
      (node (ref "D3") (pin "2") (pinfunction "K_2") (pintype "passive"))
      (node (ref "J1") (pin "5") (pinfunction "G_5") (pintype "passive"))
      (node (ref "J2") (pin "1") (pinfunction "1_1") (pintype "passive"))
      (node (ref "J5") (pin "1") (pinfunction "1_1") (pintype "passive"))
      (node (ref "L2") (pin "1") (pinfunction "1_1") (pintype "passive"))
      (node (ref "P1") (pin "3") (pinfunction "3_3") (pintype "passive"))
      (node (ref "P2") (pin "3") (pinfunction "3_3") (pintype "passive"))
      (node (ref "P3") (pin "3") (pinfunction "3_3") (pintype "passive"))
      (node (ref "P4") (pin "3") (pinfunction "3_3") (pintype "passive"))
      (node (ref "P5") (pin "3") (pinfunction "3_3") (pintype "passive"))
      (node (ref "Q2") (pin "2") (pinfunction "S_2") (pintype "passive"))
      (node (ref "Q3") (pin "2") (pinfunction "S_2") (pintype "passive"))
      (node (ref "Q4") (pin "2") (pinfunction "S_2") (pintype "passive"))
      (node (ref "Q5") (pin "2") (pinfunction "S_2") (pintype "passive"))
      (node (ref "R13") (pin "2") (pinfunction "2_2") (pintype "passive"))
      (node (ref "R15") (pin "1") (pinfunction "1_1") (pintype "passive"))
      (node (ref "R16") (pin "1") (pinfunction "1_1") (pintype "passive"))
      (node (ref "R23") (pin "1") (pinfunction "1_1") (pintype "passive"))
      (node (ref "R24") (pin "1") (pinfunction "1_1") (pintype "passive"))
      (node (ref "R25") (pin "1") (pinfunction "1_1") (pintype "passive"))
      (node (ref "R26") (pin "1") (pinfunction "1_1") (pintype "passive"))
      (node (ref "R7") (pin "1") (pinfunction "1_1") (pintype "passive"))
      (node (ref "S1") (pin "1") (pinfunction "1_1") (pintype "passive"))
      (node (ref "SWD1") (pin "2") (pinfunction "2_2") (pintype "passive"))
      (node (ref "U2") (pin "2") (pinfunction "GND_2") (pintype "passive"))
      (node (ref "U3") (pin "1") (pinfunction "GND_1") (pintype "passive"))
      (node (ref "U3") (pin "5") (pinfunction "SDO_5") (pintype "passive"))
      (node (ref "U3") (pin "7") (pinfunction "GND_7") (pintype "passive"))
      (node (ref "U4") (pin "1") (pinfunction "GND_1") (pintype "passive"))
      (node (ref "U4") (pin "7") (pinfunction "GND_7") (pintype "passive"))
      (node (ref "U5") (pin "11") (pinfunction "FSYNC_11") (pintype "passive"))
      (node (ref "U5") (pin "18") (pinfunction "GND_18") (pintype "passive"))
      (node (ref "U5") (pin "20") (pinfunction "RESV_20") (pintype "passive"))
      (node (ref "U6") (pin "12") (pinfunction "VSSA/VREF-_12") (pintype "passive"))
      (node (ref "U6") (pin "18") (pinfunction "VSS_18") (pintype "passive"))
      (node (ref "U6") (pin "31") (pinfunction "VSS_31") (pintype "passive"))
      (node (ref "U6") (pin "47") (pinfunction "VSS_47") (pintype "passive"))
      (node (ref "U6") (pin "63") (pinfunction "VSS_63") (pintype "passive"))
      (node (ref "U7") (pin "1") (pinfunction "GND_1") (pintype "passive"))
      (node (ref "U8") (pin "1") (pinfunction "GND_1") (pintype "passive"))
    )
    (net (code "45") (name "Net-(D1-Pad2)") (class "Default")
      (node (ref "D1") (pin "2") (pintype "passive"))
      (node (ref "R1") (pin "2") (pinfunction "2_2") (pintype "passive"))
    )
    (net (code "46") (name "Net-(D1-Pad3)") (class "Default")
      (node (ref "D1") (pin "3") (pintype "passive"))
      (node (ref "R2") (pin "2") (pinfunction "2_2") (pintype "passive"))
    )
    (net (code "47") (name "Net-(D1-Pad4)") (class "Default")
      (node (ref "D1") (pin "4") (pintype "passive"))
      (node (ref "R4") (pin "2") (pinfunction "2_2") (pintype "passive"))
    )
    (net (code "48") (name "Net-(D2-A)") (class "Default")
      (node (ref "D2") (pin "1") (pinfunction "A_1") (pintype "passive"))
      (node (ref "L1") (pin "2") (pinfunction "2_2") (pintype "passive"))
      (node (ref "U2") (pin "1") (pinfunction "SW_1") (pintype "passive"))
    )
    (net (code "49") (name "Net-(D2-K)") (class "Default")
      (node (ref "C2") (pin "2") (pinfunction "2_2") (pintype "passive"))
      (node (ref "C3") (pin "2") (pinfunction "2_2") (pintype "passive"))
      (node (ref "D2") (pin "2") (pinfunction "K_2") (pintype "passive"))
      (node (ref "R5") (pin "2") (pinfunction "2_2") (pintype "passive"))
      (node (ref "U1") (pin "3") (pinfunction "3_3") (pintype "passive"))
    )
    (net (code "50") (name "Net-(D3-A)") (class "Default")
      (node (ref "D3") (pin "1") (pinfunction "A_1") (pintype "passive"))
      (node (ref "R12") (pin "1") (pinfunction "1_1") (pintype "passive"))
    )
    (net (code "51") (name "Net-(D4-A)") (class "Default")
      (node (ref "C22") (pin "1") (pinfunction "1_1") (pintype "passive"))
      (node (ref "D4") (pin "1") (pinfunction "A_1") (pintype "passive"))
      (node (ref "P1") (pin "1") (pinfunction "1_1") (pintype "passive"))
      (node (ref "Q2") (pin "3") (pinfunction "D_3") (pintype "passive"))
    )
    (net (code "52") (name "Net-(D5-A)") (class "Default")
      (node (ref "C23") (pin "1") (pinfunction "1_1") (pintype "passive"))
      (node (ref "D5") (pin "1") (pinfunction "A_1") (pintype "passive"))
      (node (ref "P2") (pin "1") (pinfunction "1_1") (pintype "passive"))
      (node (ref "Q3") (pin "3") (pinfunction "D_3") (pintype "passive"))
    )
    (net (code "53") (name "Net-(D6-A)") (class "Default")
      (node (ref "C24") (pin "1") (pinfunction "1_1") (pintype "passive"))
      (node (ref "D6") (pin "1") (pinfunction "A_1") (pintype "passive"))
      (node (ref "P3") (pin "1") (pinfunction "1_1") (pintype "passive"))
      (node (ref "Q4") (pin "3") (pinfunction "D_3") (pintype "passive"))
    )
    (net (code "54") (name "Net-(D7-A)") (class "Default")
      (node (ref "C25") (pin "1") (pinfunction "1_1") (pintype "passive"))
      (node (ref "D7") (pin "1") (pinfunction "A_1") (pintype "passive"))
      (node (ref "P4") (pin "1") (pinfunction "1_1") (pintype "passive"))
      (node (ref "Q5") (pin "3") (pinfunction "D_3") (pintype "passive"))
    )
    (net (code "55") (name "Net-(J1-Pad6)") (class "Default")
      (node (ref "J1") (pin "6") (pintype "passive"))
      (node (ref "J1") (pin "7") (pintype "passive"))
      (node (ref "J1") (pin "8") (pintype "passive"))
      (node (ref "J1") (pin "9") (pintype "passive"))
      (node (ref "L2") (pin "2") (pinfunction "2_2") (pintype "passive"))
    )
    (net (code "56") (name "Net-(Q1-G)") (class "Default")
      (node (ref "Q1") (pin "1") (pinfunction "G_1") (pintype "passive"))
      (node (ref "Q6") (pin "3") (pinfunction "C_3") (pintype "passive"))
      (node (ref "R17") (pin "1") (pinfunction "1_1") (pintype "passive"))
    )
    (net (code "57") (name "Net-(Q2-G)") (class "Default")
      (node (ref "Q2") (pin "1") (pinfunction "G_1") (pintype "passive"))
      (node (ref "R18") (pin "1") (pinfunction "1_1") (pintype "passive"))
      (node (ref "R23") (pin "2") (pinfunction "2_2") (pintype "passive"))
    )
    (net (code "58") (name "Net-(Q3-G)") (class "Default")
      (node (ref "Q3") (pin "1") (pinfunction "G_1") (pintype "passive"))
      (node (ref "R19") (pin "1") (pinfunction "1_1") (pintype "passive"))
      (node (ref "R24") (pin "2") (pinfunction "2_2") (pintype "passive"))
    )
    (net (code "59") (name "Net-(Q4-G)") (class "Default")
      (node (ref "Q4") (pin "1") (pinfunction "G_1") (pintype "passive"))
      (node (ref "R20") (pin "1") (pinfunction "1_1") (pintype "passive"))
      (node (ref "R25") (pin "2") (pinfunction "2_2") (pintype "passive"))
    )
    (net (code "60") (name "Net-(Q5-G)") (class "Default")
      (node (ref "Q5") (pin "1") (pinfunction "G_1") (pintype "passive"))
      (node (ref "R21") (pin "1") (pinfunction "1_1") (pintype "passive"))
      (node (ref "R26") (pin "2") (pinfunction "2_2") (pintype "passive"))
    )
    (net (code "61") (name "Net-(Q6-B)") (class "Default")
      (node (ref "Q6") (pin "2") (pinfunction "B_2") (pintype "passive"))
      (node (ref "R22") (pin "1") (pinfunction "1_1") (pintype "passive"))
      (node (ref "R27") (pin "2") (pinfunction "2_2") (pintype "passive"))
    )
    (net (code "62") (name "Net-(Q6-E)") (class "Default")
      (node (ref "Q6") (pin "1") (pinfunction "E_1") (pintype "passive"))
      (node (ref "R27") (pin "1") (pinfunction "1_1") (pintype "passive"))
    )
    (net (code "63") (name "Net-(U2-EN)") (class "Default")
      (node (ref "R6") (pin "1") (pinfunction "1_1") (pintype "passive"))
      (node (ref "U2") (pin "4") (pinfunction "EN_4") (pintype "passive"))
    )
    (net (code "64") (name "Net-(U2-FB)") (class "Default")
      (node (ref "C3") (pin "1") (pinfunction "1_1") (pintype "passive"))
      (node (ref "R5") (pin "1") (pinfunction "1_1") (pintype "passive"))
      (node (ref "R7") (pin "2") (pinfunction "2_2") (pintype "passive"))
      (node (ref "U2") (pin "3") (pinfunction "FB_3") (pintype "passive"))
    )
    (net (code "65") (name "Net-(U5-REGOUT)") (class "Default")
      (node (ref "C15") (pin "2") (pinfunction "2_2") (pintype "passive"))
      (node (ref "U5") (pin "10") (pinfunction "REGOUT_10") (pintype "passive"))
    )
    (net (code "66") (name "Net-(U6-VCAP_1)") (class "Default")
      (node (ref "C26") (pin "2") (pinfunction "2_2") (pintype "passive"))
      (node (ref "U6") (pin "30") (pinfunction "VCAP_1_30") (pintype "passive"))
    )
    (net (code "67") (name "VBAT") (class "Default")
      (node (ref "C22") (pin "2") (pinfunction "2_2") (pintype "passive"))
      (node (ref "C23") (pin "2") (pinfunction "2_2") (pintype "passive"))
      (node (ref "C24") (pin "2") (pinfunction "2_2") (pintype "passive"))
      (node (ref "C25") (pin "2") (pinfunction "2_2") (pintype "passive"))
      (node (ref "C5") (pin "2") (pinfunction "2_2") (pintype "passive"))
      (node (ref "D4") (pin "2") (pinfunction "K_2") (pintype "passive"))
      (node (ref "D5") (pin "2") (pinfunction "K_2") (pintype "passive"))
      (node (ref "D6") (pin "2") (pinfunction "K_2") (pintype "passive"))
      (node (ref "D7") (pin "2") (pinfunction "K_2") (pintype "passive"))
      (node (ref "J2") (pin "2") (pinfunction "2_2") (pintype "passive"))
      (node (ref "L1") (pin "1") (pinfunction "1_1") (pintype "passive"))
      (node (ref "P1") (pin "2") (pinfunction "2_2") (pintype "passive"))
      (node (ref "P2") (pin "2") (pinfunction "2_2") (pintype "passive"))
      (node (ref "P3") (pin "2") (pinfunction "2_2") (pintype "passive"))
      (node (ref "P4") (pin "2") (pinfunction "2_2") (pintype "passive"))
      (node (ref "R11") (pin "1") (pinfunction "1_1") (pintype "passive"))
      (node (ref "R6") (pin "2") (pinfunction "2_2") (pintype "passive"))
      (node (ref "U2") (pin "5") (pinfunction "IN_5") (pintype "passive"))
    )
    (net (code "68") (name "VDD_IN") (class "Default")
      (node (ref "J1") (pin "1") (pinfunction "5V_1") (pintype "passive"))
      (node (ref "U1") (pin "1") (pinfunction "1_1") (pintype "passive"))
    )
    (net (code "69") (name "unconnected-(J1-ID-Pad4)") (class "Default")
      (node (ref "J1") (pin "4") (pinfunction "ID_4") (pintype "passive+no_connect"))
    )
    (net (code "70") (name "unconnected-(J4-Pad1)") (class "Default")
      (node (ref "J4") (pin "1") (pinfunction "1_1") (pintype "passive+no_connect"))
    )
    (net (code "71") (name "unconnected-(S1-Pad2)") (class "Default")
      (node (ref "S1") (pin "2") (pintype "passive"))
    )
    (net (code "72") (name "unconnected-(S1-Pad4)") (class "Default")
      (node (ref "S1") (pin "4") (pintype "passive"))
    )
    (net (code "73") (name "unconnected-(U2-NC-Pad6)") (class "Default")
      (node (ref "U2") (pin "6") (pinfunction "NC_6") (pintype "passive+no_connect"))
    )
    (net (code "74") (name "unconnected-(U5-AUX_CL-Pad7)") (class "Default")
      (node (ref "U5") (pin "7") (pinfunction "AUX_CL_7") (pintype "passive+no_connect"))
    )
    (net (code "75") (name "unconnected-(U5-AUX_DA-Pad21)") (class "Default")
      (node (ref "U5") (pin "21") (pinfunction "AUX_DA_21") (pintype "passive+no_connect"))
    )
    (net (code "76") (name "unconnected-(U5-NC-Pad2)") (class "Default")
      (node (ref "U5") (pin "2") (pinfunction "NC_2") (pintype "passive+no_connect"))
    )
    (net (code "77") (name "unconnected-(U5-NC-Pad3)") (class "Default")
      (node (ref "U5") (pin "3") (pinfunction "NC_3") (pintype "passive+no_connect"))
    )
    (net (code "78") (name "unconnected-(U5-NC-Pad4)") (class "Default")
      (node (ref "U5") (pin "4") (pinfunction "NC_4") (pintype "passive+no_connect"))
    )
    (net (code "79") (name "unconnected-(U5-NC-Pad5)") (class "Default")
      (node (ref "U5") (pin "5") (pinfunction "NC_5") (pintype "passive+no_connect"))
    )
    (net (code "80") (name "unconnected-(U5-NC-Pad6)") (class "Default")
      (node (ref "U5") (pin "6") (pinfunction "NC_6") (pintype "passive+no_connect"))
    )
    (net (code "81") (name "unconnected-(U5-NC-Pad14)") (class "Default")
      (node (ref "U5") (pin "14") (pinfunction "NC_14") (pintype "passive+no_connect"))
    )
    (net (code "82") (name "unconnected-(U5-NC-Pad15)") (class "Default")
      (node (ref "U5") (pin "15") (pinfunction "NC_15") (pintype "passive+no_connect"))
    )
    (net (code "83") (name "unconnected-(U5-NC-Pad16)") (class "Default")
      (node (ref "U5") (pin "16") (pinfunction "NC_16") (pintype "passive+no_connect"))
    )
    (net (code "84") (name "unconnected-(U5-NC-Pad17)") (class "Default")
      (node (ref "U5") (pin "17") (pinfunction "NC_17") (pintype "passive+no_connect"))
    )
    (net (code "85") (name "unconnected-(U5-RESV-Pad19)") (class "Default")
      (node (ref "U5") (pin "19") (pinfunction "RESV_19") (pintype "passive+no_connect"))
    )
    (net (code "86") (name "unconnected-(U6-PA2-Pad16)") (class "Default")
      (node (ref "U6") (pin "16") (pinfunction "PA2_16") (pintype "passive+no_connect"))
    )
    (net (code "87") (name "unconnected-(U6-PA3-Pad17)") (class "Default")
      (node (ref "U6") (pin "17") (pinfunction "PA3_17") (pintype "passive+no_connect"))
    )
    (net (code "88") (name "unconnected-(U6-PA4-Pad20)") (class "Default")
      (node (ref "U6") (pin "20") (pinfunction "PA4_20") (pintype "passive+no_connect"))
    )
    (net (code "89") (name "unconnected-(U6-PA5-Pad21)") (class "Default")
      (node (ref "U6") (pin "21") (pinfunction "PA5_21") (pintype "passive+no_connect"))
    )
    (net (code "90") (name "unconnected-(U6-PA8-Pad41)") (class "Default")
      (node (ref "U6") (pin "41") (pinfunction "PA8_41") (pintype "passive+no_connect"))
    )
    (net (code "91") (name "unconnected-(U6-PA15-Pad50)") (class "Default")
      (node (ref "U6") (pin "50") (pinfunction "PA15_50") (pintype "passive+no_connect"))
    )
    (net (code "92") (name "unconnected-(U6-PB2-Pad28)") (class "Default")
      (node (ref "U6") (pin "28") (pinfunction "PB2_28") (pintype "passive+no_connect"))
    )
    (net (code "93") (name "unconnected-(U6-PB3-Pad55)") (class "Default")
      (node (ref "U6") (pin "55") (pinfunction "PB3_55") (pintype "passive+no_connect"))
    )
    (net (code "94") (name "unconnected-(U6-PB5-Pad57)") (class "Default")
      (node (ref "U6") (pin "57") (pinfunction "PB5_57") (pintype "passive+no_connect"))
    )
    (net (code "95") (name "unconnected-(U6-PB8-Pad61)") (class "Default")
      (node (ref "U6") (pin "61") (pinfunction "PB8_61") (pintype "passive+no_connect"))
    )
    (net (code "96") (name "unconnected-(U6-PB9-Pad62)") (class "Default")
      (node (ref "U6") (pin "62") (pinfunction "PB9_62") (pintype "passive+no_connect"))
    )
    (net (code "97") (name "unconnected-(U6-PB10-Pad29)") (class "Default")
      (node (ref "U6") (pin "29") (pinfunction "PB10_29") (pintype "passive+no_connect"))
    )
    (net (code "98") (name "unconnected-(U6-PB12-Pad33)") (class "Default")
      (node (ref "U6") (pin "33") (pinfunction "PB12_33") (pintype "passive+no_connect"))
    )
    (net (code "99") (name "unconnected-(U6-PB13-Pad34)") (class "Default")
      (node (ref "U6") (pin "34") (pinfunction "PB13_34") (pintype "passive+no_connect"))
    )
    (net (code "100") (name "unconnected-(U6-PB14-Pad35)") (class "Default")
      (node (ref "U6") (pin "35") (pinfunction "PB14_35") (pintype "passive+no_connect"))
    )
    (net (code "101") (name "unconnected-(U6-PB15-Pad36)") (class "Default")
      (node (ref "U6") (pin "36") (pinfunction "PB15_36") (pintype "passive+no_connect"))
    )
    (net (code "102") (name "unconnected-(U6-PC8-Pad39)") (class "Default")
      (node (ref "U6") (pin "39") (pinfunction "PC8_39") (pintype "passive+no_connect"))
    )
    (net (code "103") (name "unconnected-(U6-PC9-Pad40)") (class "Default")
      (node (ref "U6") (pin "40") (pinfunction "PC9_40") (pintype "passive+no_connect"))
    )
    (net (code "104") (name "unconnected-(U6-PD2-Pad54)") (class "Default")
      (node (ref "U6") (pin "54") (pinfunction "PD2_54") (pintype "passive+no_connect"))
    )
  )
)
